# pic18f44k22_dip_to_tqfp.net
KiCad netlist of a schematic drawn in EAGLE
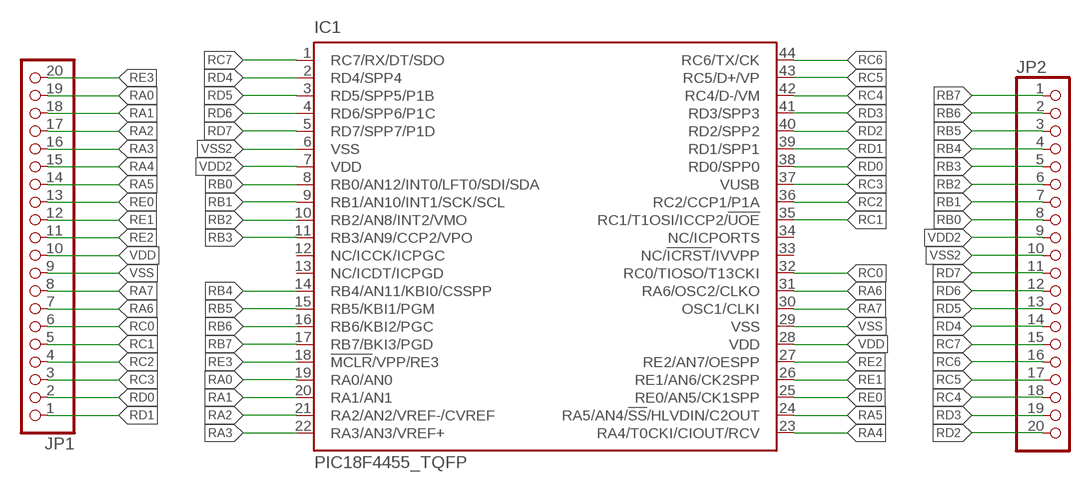
[diagram p0: schematic, sheet 1]

(export (version "E")
  (design (tool "Eeschema 10.0.6"))
  (components
    (comp (ref "IC1")
      (value "PIC18F4455_TQFP")
      (footprint "eagle-import:TQFP44")
      (fields (field (name "MF") "MICROCHIP") (field (name "MPN") "PIC18F4455-I/PT"))
      (libsource (lib "eagle-import") (part "PIC18F4_TQFP455"))
    )
    (comp (ref "JP1")
      (value "PINHD-1X20_2.54-SMD")
      (footprint "eagle-import:1X20SMD")
      (libsource (lib "eagle-import") (part "PINHD-1X20_2.54-SMD"))
    )
    (comp (ref "JP2")
      (value "PINHD-1X20_2.54-SMD")
      (footprint "eagle-import:1X20SMD")
      (libsource (lib "eagle-import") (part "PINHD-1X20_2.54-SMD"))
    )
  )
  (nets
    (net (code "1") (name "RA0") (class "Default")
      (node (ref "IC1") (pin "19") (pinfunction "RA0/AN0_19") (pintype "bidirectional"))
      (node (ref "JP1") (pin "19") (pinfunction "19_19") (pintype "passive"))
    )
    (net (code "2") (name "RA1") (class "Default")
      (node (ref "IC1") (pin "20") (pinfunction "RA1/AN1_20") (pintype "bidirectional"))
      (node (ref "JP1") (pin "18") (pinfunction "18_18") (pintype "passive"))
    )
    (net (code "3") (name "RA2") (class "Default")
      (node (ref "IC1") (pin "21") (pinfunction "RA2/AN2/VREF-/CVREF_21") (pintype "bidirectional"))
      (node (ref "JP1") (pin "17") (pinfunction "17_17") (pintype "passive"))
    )
    (net (code "4") (name "RA3") (class "Default")
      (node (ref "IC1") (pin "22") (pinfunction "RA3/AN3/VREF+_22") (pintype "bidirectional"))
      (node (ref "JP1") (pin "16") (pinfunction "16_16") (pintype "passive"))
    )
    (net (code "5") (name "RA4") (class "Default")
      (node (ref "IC1") (pin "23") (pinfunction "RA4/T0CKI/CIOUT/RCV_23") (pintype "bidirectional"))
      (node (ref "JP1") (pin "15") (pinfunction "15_15") (pintype "passive"))
    )
    (net (code "6") (name "RA5") (class "Default")
      (node (ref "IC1") (pin "24") (pinfunction "RA5/AN4/~{SS}/HLVDIN/C2OUT_24") (pintype "bidirectional"))
      (node (ref "JP1") (pin "14") (pinfunction "14_14") (pintype "passive"))
    )
    (net (code "7") (name "RA6") (class "Default")
      (node (ref "IC1") (pin "31") (pinfunction "RA6/OSC2/CLKO_31") (pintype "output"))
      (node (ref "JP1") (pin "7") (pinfunction "7_7") (pintype "passive"))
    )
    (net (code "8") (name "RA7") (class "Default")
      (node (ref "IC1") (pin "30") (pinfunction "OSC1/CLKI_30") (pintype "input"))
      (node (ref "JP1") (pin "8") (pinfunction "8_8") (pintype "passive"))
    )
    (net (code "9") (name "RB0") (class "Default")
      (node (ref "IC1") (pin "8") (pinfunction "RB0/AN12/INT0/LFT0/SDI/SDA_8") (pintype "bidirectional"))
      (node (ref "JP2") (pin "8") (pinfunction "8_8") (pintype "passive"))
    )
    (net (code "10") (name "RB1") (class "Default")
      (node (ref "IC1") (pin "9") (pinfunction "RB1/AN10/INT1/SCK/SCL_9") (pintype "bidirectional"))
      (node (ref "JP2") (pin "7") (pinfunction "7_7") (pintype "passive"))
    )
    (net (code "11") (name "RB2") (class "Default")
      (node (ref "IC1") (pin "10") (pinfunction "RB2/AN8/INT2/VMO_10") (pintype "bidirectional"))
      (node (ref "JP2") (pin "6") (pinfunction "6_6") (pintype "passive"))
    )
    (net (code "12") (name "RB3") (class "Default")
      (node (ref "IC1") (pin "11") (pinfunction "RB3/AN9/CCP2/VPO_11") (pintype "bidirectional"))
      (node (ref "JP2") (pin "5") (pinfunction "5_5") (pintype "passive"))
    )
    (net (code "13") (name "RB4") (class "Default")
      (node (ref "IC1") (pin "14") (pinfunction "RB4/AN11/KBI0/CSSPP_14") (pintype "bidirectional"))
      (node (ref "JP2") (pin "4") (pinfunction "4_4") (pintype "passive"))
    )
    (net (code "14") (name "RB5") (class "Default")
      (node (ref "IC1") (pin "15") (pinfunction "RB5/KBI1/PGM_15") (pintype "bidirectional"))
      (node (ref "JP2") (pin "3") (pinfunction "3_3") (pintype "passive"))
    )
    (net (code "15") (name "RB6") (class "Default")
      (node (ref "IC1") (pin "16") (pinfunction "RB6/KBI2/PGC_16") (pintype "bidirectional"))
      (node (ref "JP2") (pin "2") (pinfunction "2_2") (pintype "passive"))
    )
    (net (code "16") (name "RB7") (class "Default")
      (node (ref "IC1") (pin "17") (pinfunction "RB7/BKI3/PGD_17") (pintype "bidirectional"))
      (node (ref "JP2") (pin "1") (pinfunction "1_1") (pintype "passive"))
    )
    (net (code "17") (name "RC0") (class "Default")
      (node (ref "IC1") (pin "32") (pinfunction "RC0/TIOSO/T13CKI_32") (pintype "bidirectional"))
      (node (ref "JP1") (pin "6") (pinfunction "6_6") (pintype "passive"))
    )
    (net (code "18") (name "RC1") (class "Default")
      (node (ref "IC1") (pin "35") (pinfunction "RC1/T1OSI/ICCP2/~{UOE}_35") (pintype "bidirectional"))
      (node (ref "JP1") (pin "5") (pinfunction "5_5") (pintype "passive"))
    )
    (net (code "19") (name "RC2") (class "Default")
      (node (ref "IC1") (pin "36") (pinfunction "RC2/CCP1/P1A_36") (pintype "bidirectional"))
      (node (ref "JP1") (pin "4") (pinfunction "4_4") (pintype "passive"))
    )
    (net (code "20") (name "RC3") (class "Default")
      (node (ref "IC1") (pin "37") (pinfunction "VUSB_37") (pintype "bidirectional"))
      (node (ref "JP1") (pin "3") (pinfunction "3_3") (pintype "passive"))
    )
    (net (code "21") (name "RC4") (class "Default")
      (node (ref "IC1") (pin "42") (pinfunction "RC4/D-/VM_42") (pintype "bidirectional"))
      (node (ref "JP2") (pin "18") (pinfunction "18_18") (pintype "passive"))
    )
    (net (code "22") (name "RC5") (class "Default")
      (node (ref "IC1") (pin "43") (pinfunction "RC5/D+/VP_43") (pintype "bidirectional"))
      (node (ref "JP2") (pin "17") (pinfunction "17_17") (pintype "passive"))
    )
    (net (code "23") (name "RC6") (class "Default")
      (node (ref "IC1") (pin "44") (pinfunction "RC6/TX/CK_44") (pintype "bidirectional"))
      (node (ref "JP2") (pin "16") (pinfunction "16_16") (pintype "passive"))
    )
    (net (code "24") (name "RC7") (class "Default")
      (node (ref "IC1") (pin "1") (pinfunction "RC7/RX/DT/SDO_1") (pintype "bidirectional"))
      (node (ref "JP2") (pin "15") (pinfunction "15_15") (pintype "passive"))
    )
    (net (code "25") (name "RD0") (class "Default")
      (node (ref "IC1") (pin "38") (pinfunction "RD0/SPP0_38") (pintype "bidirectional"))
      (node (ref "JP1") (pin "2") (pinfunction "2_2") (pintype "passive"))
    )
    (net (code "26") (name "RD1") (class "Default")
      (node (ref "IC1") (pin "39") (pinfunction "RD1/SPP1_39") (pintype "bidirectional"))
      (node (ref "JP1") (pin "1") (pinfunction "1_1") (pintype "passive"))
    )
    (net (code "27") (name "RD2") (class "Default")
      (node (ref "IC1") (pin "40") (pinfunction "RD2/SPP2_40") (pintype "bidirectional"))
      (node (ref "JP2") (pin "20") (pinfunction "20_20") (pintype "passive"))
    )
    (net (code "28") (name "RD3") (class "Default")
      (node (ref "IC1") (pin "41") (pinfunction "RD3/SPP3_41") (pintype "bidirectional"))
      (node (ref "JP2") (pin "19") (pinfunction "19_19") (pintype "passive"))
    )
    (net (code "29") (name "RD4") (class "Default")
      (node (ref "IC1") (pin "2") (pinfunction "RD4/SPP4_2") (pintype "bidirectional"))
      (node (ref "JP2") (pin "14") (pinfunction "14_14") (pintype "passive"))
    )
    (net (code "30") (name "RD5") (class "Default")
      (node (ref "IC1") (pin "3") (pinfunction "RD5/SPP5/P1B_3") (pintype "bidirectional"))
      (node (ref "JP2") (pin "13") (pinfunction "13_13") (pintype "passive"))
    )
    (net (code "31") (name "RD6") (class "Default")
      (node (ref "IC1") (pin "4") (pinfunction "RD6/SPP6/P1C_4") (pintype "bidirectional"))
      (node (ref "JP2") (pin "12") (pinfunction "12_12") (pintype "passive"))
    )
    (net (code "32") (name "RD7") (class "Default")
      (node (ref "IC1") (pin "5") (pinfunction "RD7/SPP7/P1D_5") (pintype "bidirectional"))
      (node (ref "JP2") (pin "11") (pinfunction "11_11") (pintype "passive"))
    )
    (net (code "33") (name "RE0") (class "Default")
      (node (ref "IC1") (pin "25") (pinfunction "RE0/AN5/CK1SPP_25") (pintype "bidirectional"))
      (node (ref "JP1") (pin "13") (pinfunction "13_13") (pintype "passive"))
    )
    (net (code "34") (name "RE1") (class "Default")
      (node (ref "IC1") (pin "26") (pinfunction "RE1/AN6/CK2SPP_26") (pintype "bidirectional"))
      (node (ref "JP1") (pin "12") (pinfunction "12_12") (pintype "passive"))
    )
    (net (code "35") (name "RE2") (class "Default")
      (node (ref "IC1") (pin "27") (pinfunction "RE2/AN7/OESPP_27") (pintype "bidirectional"))
      (node (ref "JP1") (pin "11") (pinfunction "11_11") (pintype "passive"))
    )
    (net (code "36") (name "RE3") (class "Default")
      (node (ref "IC1") (pin "18") (pinfunction "~{MCLR}/VPP/RE3_18") (pintype "input"))
      (node (ref "JP1") (pin "20") (pinfunction "20_20") (pintype "passive"))
    )
    (net (code "37") (name "VDD") (class "Default")
      (node (ref "IC1") (pin "28") (pinfunction "VDD_28") (pintype "power_in"))
      (node (ref "JP1") (pin "10") (pinfunction "10_10") (pintype "passive"))
    )
    (net (code "38") (name "VDD2") (class "Default")
      (node (ref "IC1") (pin "7") (pinfunction "VDD_7") (pintype "power_in"))
      (node (ref "JP2") (pin "9") (pinfunction "9_9") (pintype "passive"))
    )
    (net (code "39") (name "VSS") (class "Default")
      (node (ref "IC1") (pin "29") (pinfunction "VSS_29") (pintype "power_in"))
      (node (ref "JP1") (pin "9") (pinfunction "9_9") (pintype "passive"))
    )
    (net (code "40") (name "VSS2") (class "Default")
      (node (ref "IC1") (pin "6") (pinfunction "VSS_6") (pintype "power_in"))
      (node (ref "JP2") (pin "10") (pinfunction "10_10") (pintype "passive"))
    )
    (net (code "41") (name "unconnected-(IC1-NC{slash}ICCK{slash}ICPGC-Pad12)") (class "Default")
      (node (ref "IC1") (pin "12") (pinfunction "NC/ICCK/ICPGC_12") (pintype "bidirectional"))
    )
    (net (code "42") (name "unconnected-(IC1-NC{slash}ICDT{slash}ICPGD-Pad13)") (class "Default")
      (node (ref "IC1") (pin "13") (pinfunction "NC/ICDT/ICPGD_13") (pintype "bidirectional"))
    )
    (net (code "43") (name "unconnected-(IC1-NC{slash}ICPORTS-Pad34)") (class "Default")
      (node (ref "IC1") (pin "34") (pinfunction "NC/ICPORTS_34") (pintype "input"))
    )
    (net (code "44") (name "unconnected-(IC1-NC{slash}~{ICRST}{slash}IVVPP-Pad33)") (class "Default")
      (node (ref "IC1") (pin "33") (pinfunction "NC/~{ICRST}/IVVPP_33") (pintype "input"))
    )
  )
)
